# air_qulity_monitor.net
KiCad netlist of a schematic drawn in Altium Designer
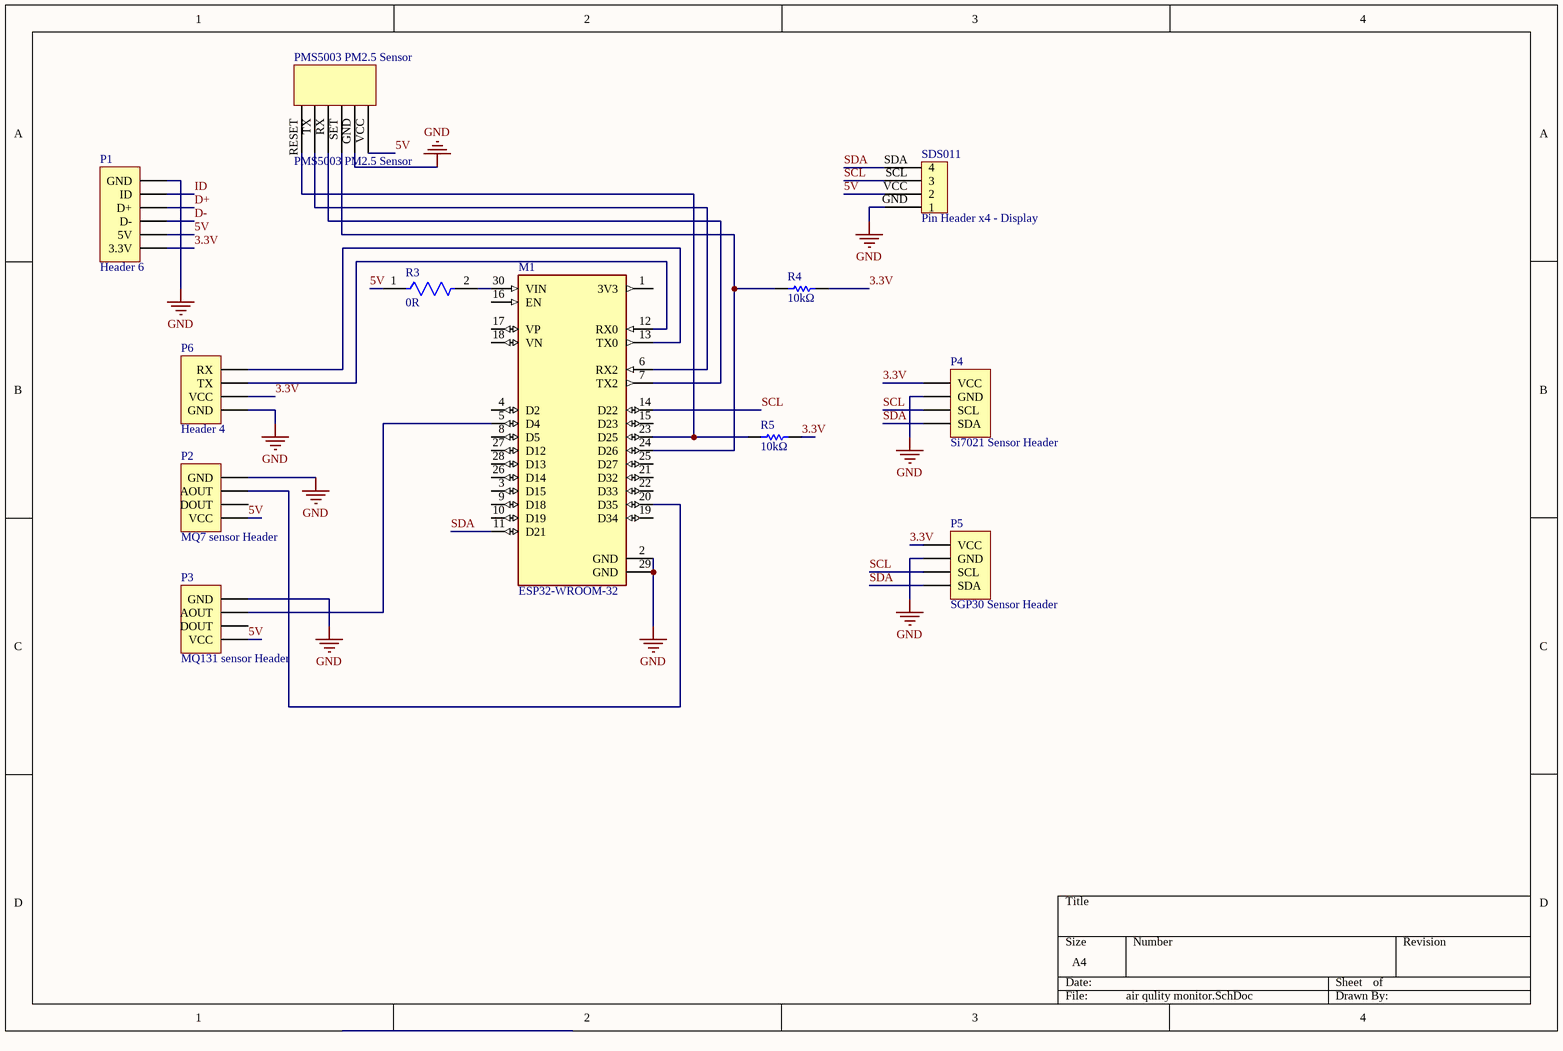
[diagram p0: air qulity monitor.SchDoc]

(export (version "E")
  (design (tool "Eeschema 10.0.6"))
  (components
    (comp (ref "M1")
      (value "ESP32-WROOM-32")
      (footprint "ESP32-DEVKIT-V1")
      (libsource (lib "Modules") (part "ESP32-DEVKIT-V1"))
    )
    (comp (ref "P1")
      (value "Header 6")
      (footprint "HDR1X6")
      (description "Header, 6-Pin")
      (fields (field (name "PUBLISHER") "Altium Limited"))
      (libsource (lib "Miscellaneous Connectors") (part "Header 6"))
    )
    (comp (ref "P2")
      (value "MQ7 sensor Header")
      (footprint "HDR1X4")
      (description "Header, 4-Pin")
      (fields (field (name "PUBLISHER") "Altium Limited"))
      (libsource (lib "") (part "Header 4_1"))
    )
    (comp (ref "P3")
      (value "MQ131 sensor Header")
      (footprint "HDR1X4")
      (description "Header, 4-Pin")
      (fields (field (name "PUBLISHER") "Altium Limited"))
      (libsource (lib "") (part "Header 4_1"))
    )
    (comp (ref "P4")
      (value "Si7021 Sensor Header")
      (footprint "HDR1X4")
      (description "Header, 4-Pin")
      (fields (field (name "PUBLISHER") "Altium Limited"))
      (libsource (lib "Miscellaneous Connectors") (part "Header 4"))
    )
    (comp (ref "P5")
      (value "SGP30 Sensor Header")
      (footprint "HDR1X4")
      (description "Header, 4-Pin")
      (fields (field (name "PUBLISHER") "Altium Limited"))
      (libsource (lib "Miscellaneous Connectors") (part "Header 4"))
    )
    (comp (ref "P6")
      (value "Header 4")
      (footprint "HDR1X4")
      (description "Header, 4-Pin")
      (fields (field (name "PUBLISHER") "Altium Limited"))
      (libsource (lib "") (part "Header 4_1"))
    )
    (comp (ref "PMS5003 PM2.5 Sensor")
      (value "PMS5003 PM2.5 Sensor")
      (footprint "PMS5003 PM2.5 Sensor")
      (libsource (lib "DIY Air Quality Monitor Library") (part "PMS5003 PM2.5 Sensor"))
    )
    (comp (ref "R3")
      (value "0R")
      (footprint "FP-RC0402-0_4-IPC_A")
      (description "RES SMD 0 OHM JUMPER 1/16W 0402")
      (fields (field (name "MANUFACTURER") "Yageo") (field (name "LCSC PART #") "C106231"))
      (libsource (lib "Altium Content Vault") (part "1029c3af85768c4190bb7ad29bc67b5"))
    )
    (comp (ref "R4")
      (value "10kΩ")
      (footprint "RESC1005X40X25LL05T10")
      (description "62.5mW 50V ±100ppm/℃ ±1% -55℃~+155℃ 10kΩ 0402 Chip Resistor - Surface Mount ROHS")
      (fields (field (name "MFR. PART #") "RC0402FR-0710KL") (field (name "MANUFACTURER") "Yageo / Phycomp"))
      (libsource (lib "Altium Content Vault") (part "RES"))
    )
    (comp (ref "R5")
      (value "10kΩ")
      (footprint "RESC1005X40X25LL05T10")
      (description "62.5mW 50V ±100ppm/℃ ±1% -55℃~+155℃ 10kΩ 0402 Chip Resistor - Surface Mount ROHS")
      (fields (field (name "MFR. PART #") "RC0402FR-0710KL") (field (name "MANUFACTURER") "Yageo / Phycomp"))
      (libsource (lib "Altium Content Vault") (part "RES"))
    )
    (comp (ref "SDS011")
      (value "Pin Header x4 - Display")
      (footprint "dispay")
      (libsource (lib "display") (part "Pin Header x4 - Display"))
    )
  )
  (nets
    (net (code "1") (name "/3.3V") (class "Default")
      (node (ref "P1") (pin "1") (pinfunction "3.3V_1") (pintype "passive"))
      (node (ref "P4") (pin "1") (pinfunction "VCC_1") (pintype "passive"))
      (node (ref "P5") (pin "1") (pinfunction "VCC_1") (pintype "passive"))
      (node (ref "P6") (pin "2") (pinfunction "DOUT_2") (pintype "passive"))
      (node (ref "R4") (pin "2") (pinfunction "2_2") (pintype "passive"))
      (node (ref "R5") (pin "2") (pinfunction "2_2") (pintype "passive"))
    )
    (net (code "2") (name "/5V") (class "Default")
      (node (ref "P1") (pin "2") (pinfunction "5V_2") (pintype "passive"))
      (node (ref "P2") (pin "1") (pinfunction "VCC_1") (pintype "passive"))
      (node (ref "P3") (pin "1") (pinfunction "VCC_1") (pintype "passive"))
      (node (ref "PMS5003 PM2.5 Sensor") (pin "VCC") (pintype "passive"))
      (node (ref "R3") (pin "1") (pinfunction "1_1") (pintype "passive"))
      (node (ref "SDS011") (pin "VCC") (pinfunction "2_VCC") (pintype "passive"))
    )
    (net (code "3") (name "/D+") (class "Default")
      (node (ref "P1") (pin "4") (pinfunction "D+_4") (pintype "passive"))
    )
    (net (code "4") (name "/D-") (class "Default")
      (node (ref "P1") (pin "3") (pinfunction "D-_3") (pintype "passive"))
    )
    (net (code "5") (name "/ID") (class "Default")
      (node (ref "P1") (pin "5") (pinfunction "ID_5") (pintype "passive"))
    )
    (net (code "6") (name "/SCL") (class "Default")
      (node (ref "M1") (pin "14") (pinfunction "D22_14") (pintype "bidirectional"))
      (node (ref "P4") (pin "3") (pinfunction "SCL_3") (pintype "passive"))
      (node (ref "P5") (pin "3") (pinfunction "SCL_3") (pintype "passive"))
      (node (ref "SDS011") (pin "SCL") (pinfunction "3_SCL") (pintype "passive"))
    )
    (net (code "7") (name "/SDA") (class "Default")
      (node (ref "M1") (pin "11") (pinfunction "D21_11") (pintype "bidirectional"))
      (node (ref "P4") (pin "4") (pinfunction "SDA_4") (pintype "passive"))
      (node (ref "P5") (pin "4") (pinfunction "SDA_4") (pintype "passive"))
      (node (ref "SDS011") (pin "SDA") (pinfunction "4_SDA") (pintype "passive"))
    )
    (net (code "8") (name "GND") (class "Default")
      (node (ref "M1") (pin "2") (pinfunction "GND_2") (pintype "power_in"))
      (node (ref "M1") (pin "29") (pinfunction "GND_29") (pintype "power_in"))
      (node (ref "P1") (pin "6") (pinfunction "GND_6") (pintype "passive"))
      (node (ref "P2") (pin "4") (pinfunction "GND_4") (pintype "passive"))
      (node (ref "P3") (pin "4") (pinfunction "GND_4") (pintype "passive"))
      (node (ref "P4") (pin "2") (pinfunction "GND_2") (pintype "passive"))
      (node (ref "P5") (pin "2") (pinfunction "GND_2") (pintype "passive"))
      (node (ref "P6") (pin "1") (pinfunction "VCC_1") (pintype "passive"))
      (node (ref "PMS5003 PM2.5 Sensor") (pin "GND") (pintype "passive"))
      (node (ref "SDS011") (pin "GND") (pinfunction "1_GND") (pintype "passive"))
    )
    (net (code "9") (name "Net-(M1-D4)") (class "Default")
      (node (ref "M1") (pin "5") (pinfunction "D4_5") (pintype "bidirectional"))
      (node (ref "P3") (pin "3") (pinfunction "AOUT_3") (pintype "passive"))
    )
    (net (code "10") (name "Net-(M1-D25)") (class "Default")
      (node (ref "M1") (pin "23") (pinfunction "D25_23") (pintype "bidirectional"))
      (node (ref "PMS5003 PM2.5 Sensor") (pin "RESET") (pintype "passive"))
      (node (ref "R5") (pin "1") (pinfunction "1_1") (pintype "passive"))
    )
    (net (code "11") (name "Net-(M1-D26)") (class "Default")
      (node (ref "M1") (pin "24") (pinfunction "D26_24") (pintype "bidirectional"))
      (node (ref "PMS5003 PM2.5 Sensor") (pin "SET") (pintype "passive"))
      (node (ref "R4") (pin "1") (pinfunction "1_1") (pintype "passive"))
    )
    (net (code "12") (name "Net-(M1-D35)") (class "Default")
      (node (ref "M1") (pin "20") (pinfunction "D35_20") (pintype "bidirectional"))
      (node (ref "P2") (pin "3") (pinfunction "AOUT_3") (pintype "passive"))
    )
    (net (code "13") (name "Net-(M1-RX0)") (class "Default")
      (node (ref "M1") (pin "12") (pinfunction "RX0_12") (pintype "input"))
      (node (ref "P6") (pin "3") (pinfunction "AOUT_3") (pintype "passive"))
    )
    (net (code "14") (name "Net-(M1-RX2)") (class "Default")
      (node (ref "M1") (pin "6") (pinfunction "RX2_6") (pintype "input"))
      (node (ref "PMS5003 PM2.5 Sensor") (pin "TX") (pintype "passive"))
    )
    (net (code "15") (name "Net-(M1-TX0)") (class "Default")
      (node (ref "M1") (pin "13") (pinfunction "TX0_13") (pintype "output"))
      (node (ref "P6") (pin "4") (pinfunction "GND_4") (pintype "passive"))
    )
    (net (code "16") (name "Net-(M1-TX2)") (class "Default")
      (node (ref "M1") (pin "7") (pinfunction "TX2_7") (pintype "output"))
      (node (ref "PMS5003 PM2.5 Sensor") (pin "RX") (pintype "passive"))
    )
    (net (code "17") (name "Net-(M1-VIN)") (class "Default")
      (node (ref "M1") (pin "30") (pinfunction "VIN_30") (pintype "input"))
      (node (ref "R3") (pin "2") (pinfunction "2_2") (pintype "passive"))
    )
    (net (code "18") (name "unconnected-(M1-3V3-Pad1)") (class "Default")
      (node (ref "M1") (pin "1") (pinfunction "3V3_1") (pintype "output"))
    )
    (net (code "19") (name "unconnected-(M1-D2-Pad4)") (class "Default")
      (node (ref "M1") (pin "4") (pinfunction "D2_4") (pintype "bidirectional"))
    )
    (net (code "20") (name "unconnected-(M1-D5-Pad8)") (class "Default")
      (node (ref "M1") (pin "8") (pinfunction "D5_8") (pintype "bidirectional"))
    )
    (net (code "21") (name "unconnected-(M1-D12-Pad27)") (class "Default")
      (node (ref "M1") (pin "27") (pinfunction "D12_27") (pintype "bidirectional"))
    )
    (net (code "22") (name "unconnected-(M1-D13-Pad28)") (class "Default")
      (node (ref "M1") (pin "28") (pinfunction "D13_28") (pintype "bidirectional"))
    )
    (net (code "23") (name "unconnected-(M1-D14-Pad26)") (class "Default")
      (node (ref "M1") (pin "26") (pinfunction "D14_26") (pintype "bidirectional"))
    )
    (net (code "24") (name "unconnected-(M1-D15-Pad3)") (class "Default")
      (node (ref "M1") (pin "3") (pinfunction "D15_3") (pintype "bidirectional"))
    )
    (net (code "25") (name "unconnected-(M1-D18-Pad9)") (class "Default")
      (node (ref "M1") (pin "9") (pinfunction "D18_9") (pintype "bidirectional"))
    )
    (net (code "26") (name "unconnected-(M1-D19-Pad10)") (class "Default")
      (node (ref "M1") (pin "10") (pinfunction "D19_10") (pintype "bidirectional"))
    )
    (net (code "27") (name "unconnected-(M1-D23-Pad15)") (class "Default")
      (node (ref "M1") (pin "15") (pinfunction "D23_15") (pintype "bidirectional"))
    )
    (net (code "28") (name "unconnected-(M1-D27-Pad25)") (class "Default")
      (node (ref "M1") (pin "25") (pinfunction "D27_25") (pintype "bidirectional"))
    )
    (net (code "29") (name "unconnected-(M1-D32-Pad21)") (class "Default")
      (node (ref "M1") (pin "21") (pinfunction "D32_21") (pintype "bidirectional"))
    )
    (net (code "30") (name "unconnected-(M1-D33-Pad22)") (class "Default")
      (node (ref "M1") (pin "22") (pinfunction "D33_22") (pintype "bidirectional"))
    )
    (net (code "31") (name "unconnected-(M1-D34-Pad19)") (class "Default")
      (node (ref "M1") (pin "19") (pinfunction "D34_19") (pintype "bidirectional"))
    )
    (net (code "32") (name "unconnected-(M1-EN-Pad16)") (class "Default")
      (node (ref "M1") (pin "16") (pinfunction "EN_16") (pintype "input"))
    )
    (net (code "33") (name "unconnected-(M1-VN-Pad18)") (class "Default")
      (node (ref "M1") (pin "18") (pinfunction "VN_18") (pintype "bidirectional"))
    )
    (net (code "34") (name "unconnected-(M1-VP-Pad17)") (class "Default")
      (node (ref "M1") (pin "17") (pinfunction "VP_17") (pintype "bidirectional"))
    )
    (net (code "35") (name "unconnected-(P2-DOUT-Pad2)") (class "Default")
      (node (ref "P2") (pin "2") (pinfunction "DOUT_2") (pintype "passive"))
    )
    (net (code "36") (name "unconnected-(P3-DOUT-Pad2)") (class "Default")
      (node (ref "P3") (pin "2") (pinfunction "DOUT_2") (pintype "passive"))
    )
  )
)
